# 00-OVERVIEW.net
KiCad netlist of a schematic drawn in Altium Designer
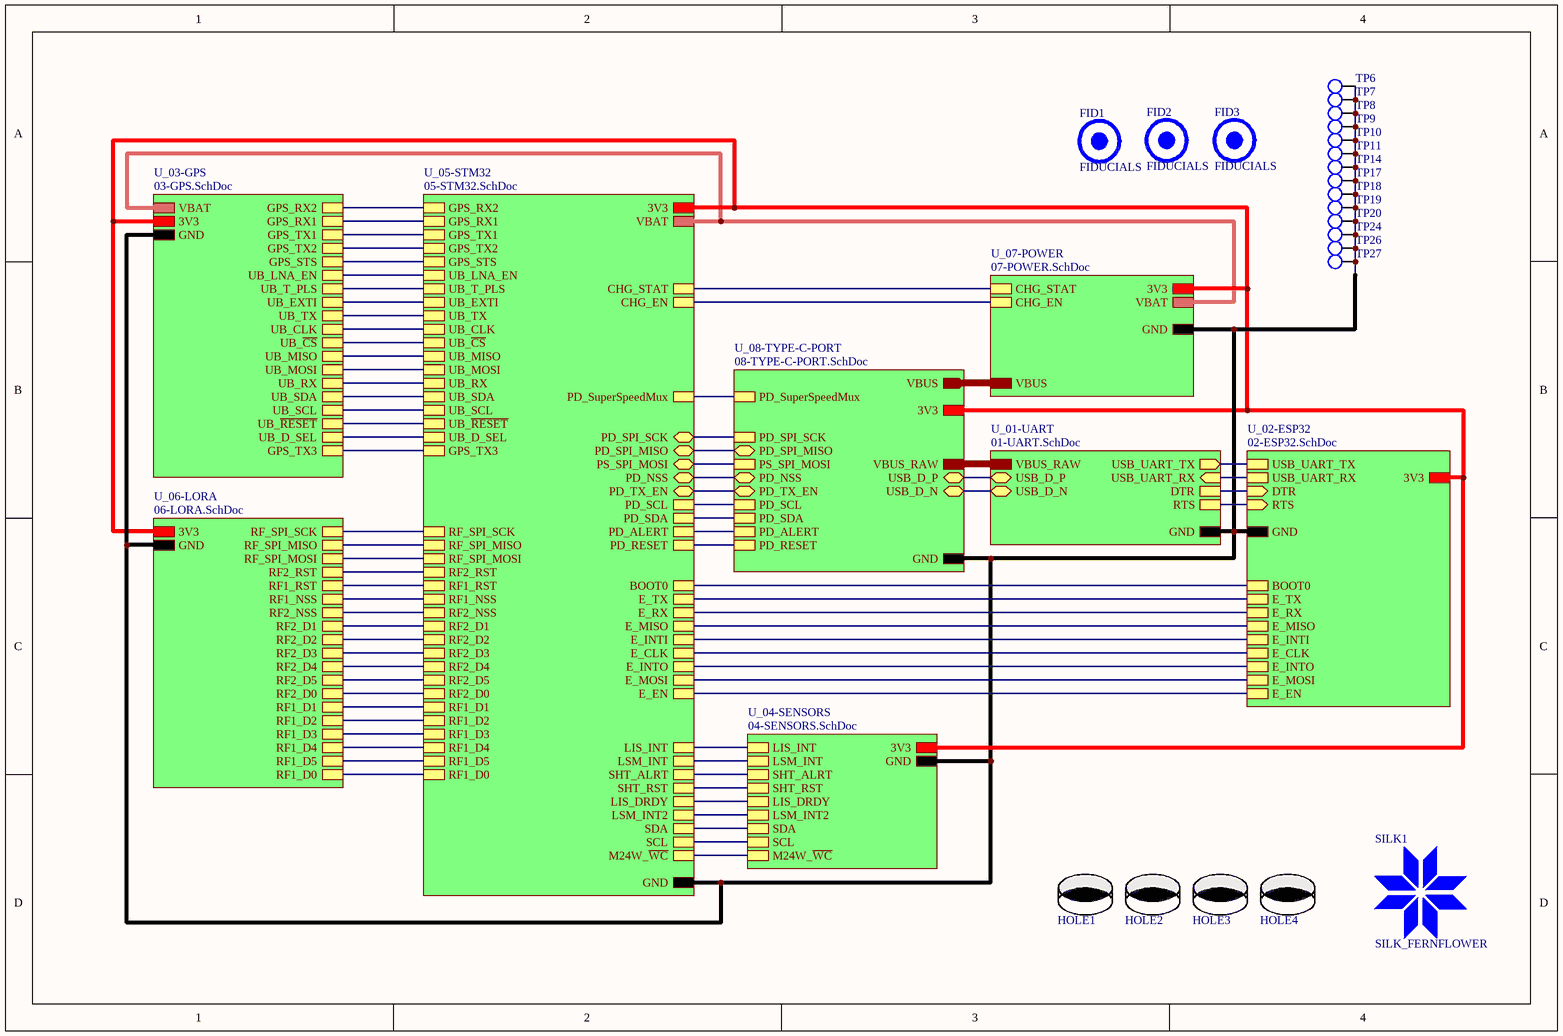
[diagram p0: 00-OVERVIEW.SchDoc]

(export (version "E")
  (design (tool "Eeschema 10.0.6"))
  (components
    (comp (ref "FID1")
      (value "FIDUCIALS")
      (footprint "FID_C_2-1")
      (libsource (lib "ComponentsLib") (part "FIDUCIALS"))
    )
    (comp (ref "FID2")
      (value "FIDUCIALS")
      (footprint "FID_C_5-3-1")
      (libsource (lib "ComponentsLib") (part "FIDUCIALS"))
    )
    (comp (ref "FID3")
      (value "FIDUCIALS")
      (footprint "FID_C_2-1")
      (libsource (lib "ComponentsLib") (part "FIDUCIALS"))
    )
    (comp (ref "HOLE1")
      (value "HOLE_M3")
      (footprint "HOLE_M3")
      (libsource (lib "ComponentsLib") (part "HOLE_M3"))
    )
    (comp (ref "HOLE2")
      (value "HOLE_M3")
      (footprint "HOLE_M3")
      (libsource (lib "ComponentsLib") (part "HOLE_M3"))
    )
    (comp (ref "HOLE3")
      (value "HOLE_M3")
      (footprint "HOLE_M3")
      (libsource (lib "ComponentsLib") (part "HOLE_M3"))
    )
    (comp (ref "HOLE4")
      (value "HOLE_M3")
      (footprint "HOLE_M3")
      (libsource (lib "ComponentsLib") (part "HOLE_M3"))
    )
    (comp (ref "SILK1")
      (value "SILK_FERNFLOWER")
      (footprint "SILK_FERNFLOWER")
      (libsource (lib "ComponentsLib") (part "SILK_FERNFLOWER"))
    )
    (comp (ref "TP6")
      (value "TEST_POINT")
      (footprint "THOOK_0.8-1")
      (libsource (lib "ComponentsLib") (part "TEST_POINT"))
    )
    (comp (ref "TP7")
      (value "TEST_POINT")
      (footprint "THOOK_0.8-1")
      (libsource (lib "ComponentsLib") (part "TEST_POINT"))
    )
    (comp (ref "TP8")
      (value "TEST_POINT")
      (footprint "THOOK_0.8-1")
      (libsource (lib "ComponentsLib") (part "TEST_POINT"))
    )
    (comp (ref "TP9")
      (value "TEST_POINT")
      (footprint "THOOK_0.8-1")
      (libsource (lib "ComponentsLib") (part "TEST_POINT"))
    )
    (comp (ref "TP10")
      (value "TEST_POINT")
      (footprint "THOOK_0.8-1")
      (libsource (lib "ComponentsLib") (part "TEST_POINT"))
    )
    (comp (ref "TP11")
      (value "TEST_POINT")
      (footprint "THOOK_0.8-1")
      (libsource (lib "ComponentsLib") (part "TEST_POINT"))
    )
    (comp (ref "TP14")
      (value "TEST_POINT")
      (footprint "THOOK_0.8-1")
      (libsource (lib "ComponentsLib") (part "TEST_POINT"))
    )
    (comp (ref "TP17")
      (value "TEST_POINT")
      (footprint "THOOK_0.8-1")
      (libsource (lib "ComponentsLib") (part "TEST_POINT"))
    )
    (comp (ref "TP18")
      (value "TEST_POINT")
      (footprint "THOOK_0.8-1")
      (libsource (lib "ComponentsLib") (part "TEST_POINT"))
    )
    (comp (ref "TP19")
      (value "TEST_POINT")
      (footprint "THOOK_0.8-1")
      (libsource (lib "ComponentsLib") (part "TEST_POINT"))
    )
    (comp (ref "TP20")
      (value "TEST_POINT")
      (footprint "THOOK_0.8-1")
      (libsource (lib "ComponentsLib") (part "TEST_POINT"))
    )
    (comp (ref "TP24")
      (value "TEST_POINT")
      (footprint "THOOK_0.8-1")
      (libsource (lib "ComponentsLib") (part "TEST_POINT"))
    )
    (comp (ref "TP26")
      (value "TEST_POINT")
      (footprint "THOOK_0.8-1")
      (libsource (lib "ComponentsLib") (part "TEST_POINT"))
    )
    (comp (ref "TP27")
      (value "TEST_POINT")
      (footprint "THOOK_0.8-1")
      (libsource (lib "ComponentsLib") (part "TEST_POINT"))
    )
  )
  (nets
    (net (code "14") (name "/GND") (class "Default")
      (node (ref "TP10") (pin "1") (pinfunction "1_1") (pintype "passive"))
      (node (ref "TP11") (pin "1") (pinfunction "1_1") (pintype "passive"))
      (node (ref "TP14") (pin "1") (pinfunction "1_1") (pintype "passive"))
      (node (ref "TP17") (pin "1") (pinfunction "1_1") (pintype "passive"))
      (node (ref "TP18") (pin "1") (pinfunction "1_1") (pintype "passive"))
      (node (ref "TP19") (pin "1") (pinfunction "1_1") (pintype "passive"))
      (node (ref "TP20") (pin "1") (pinfunction "1_1") (pintype "passive"))
      (node (ref "TP24") (pin "1") (pinfunction "1_1") (pintype "passive"))
      (node (ref "TP26") (pin "1") (pinfunction "1_1") (pintype "passive"))
      (node (ref "TP27") (pin "1") (pinfunction "1_1") (pintype "passive"))
      (node (ref "TP6") (pin "1") (pinfunction "1_1") (pintype "passive"))
      (node (ref "TP7") (pin "1") (pinfunction "1_1") (pintype "passive"))
      (node (ref "TP8") (pin "1") (pinfunction "1_1") (pintype "passive"))
      (node (ref "TP9") (pin "1") (pinfunction "1_1") (pintype "passive"))
    )
    (net (code "80") (name "unconnected-(HOLE1-Pad4)") (class "Default")
      (node (ref "HOLE1") (pin "4") (pinfunction "4_4") (pintype "passive"))
    )
    (net (code "81") (name "unconnected-(HOLE2-Pad4)") (class "Default")
      (node (ref "HOLE2") (pin "4") (pinfunction "4_4") (pintype "passive"))
    )
    (net (code "82") (name "unconnected-(HOLE3-Pad4)") (class "Default")
      (node (ref "HOLE3") (pin "4") (pinfunction "4_4") (pintype "passive"))
    )
    (net (code "83") (name "unconnected-(HOLE4-Pad4)") (class "Default")
      (node (ref "HOLE4") (pin "4") (pinfunction "4_4") (pintype "passive"))
    )
  )
)
